# Door_Buttons.net
KiCad netlist of a schematic drawn in Altium Designer
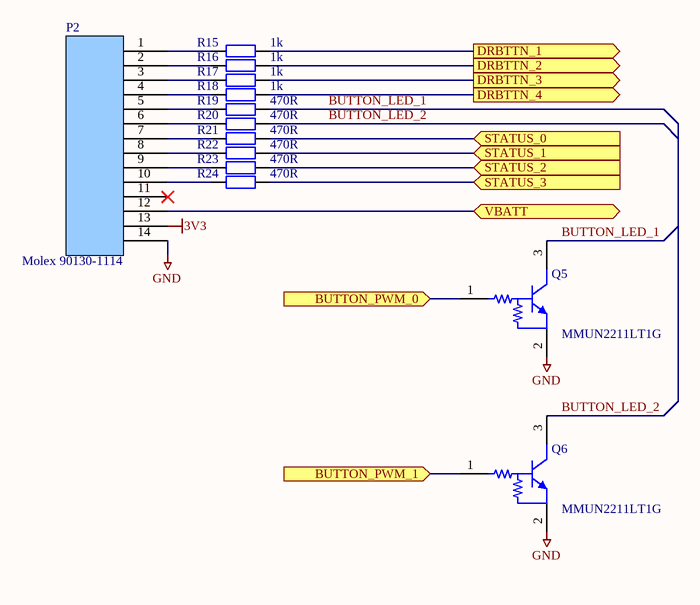
[diagram p0: Door Buttons.SchDoc]

(export (version "E")
  (design (tool "Eeschema 10.0.6"))
  (components
    (comp (ref "P2")
      (value "Molex 90130-1114")
      (footprint "PCB-642648-1")
      (description "Conn Shrouded Header HDR 14 POS 2.54mm Solder ST Thru-Hole C-Grid IIIáTray")
      (fields (field (name "MANUFACTURER PART NUMBER") "90130-1114"))
      (libsource (lib "FavoritesLibrary") (part "SYM-642648-1"))
    )
    (comp (ref "Q5")
      (value "MMUN2211LT1G")
      (footprint "ONSC-SOT-23-3-318-08_V")
      (libsource (lib "CommunityVault") (part "ONSC-BRT-NPN-B1E2C3-3"))
    )
    (comp (ref "Q6")
      (value "MMUN2211LT1G")
      (footprint "ONSC-SOT-23-3-318-08_V")
      (libsource (lib "CommunityVault") (part "ONSC-BRT-NPN-B1E2C3-3"))
    )
    (comp (ref "R15")
      (value "1k")
      (footprint "PCB-3652081-2")
      (description "GENERIC 0805 RESISTOR")
      (libsource (lib "FavoritesLibrary") (part "SYM-rprrpiwz7au7w5x5ojb2-1"))
    )
    (comp (ref "R16")
      (value "1k")
      (footprint "PCB-3652081-2")
      (description "GENERIC 0805 RESISTOR")
      (libsource (lib "FavoritesLibrary") (part "SYM-rprrpiwz7au7w5x5ojb2-1"))
    )
    (comp (ref "R17")
      (value "1k")
      (footprint "PCB-3652081-2")
      (description "GENERIC 0805 RESISTOR")
      (libsource (lib "FavoritesLibrary") (part "SYM-rprrpiwz7au7w5x5ojb2-1"))
    )
    (comp (ref "R18")
      (value "1k")
      (footprint "PCB-3652081-2")
      (description "GENERIC 0805 RESISTOR")
      (libsource (lib "FavoritesLibrary") (part "SYM-rprrpiwz7au7w5x5ojb2-1"))
    )
    (comp (ref "R19")
      (value "470R")
      (footprint "PCB-3652081-2")
      (description "GENERIC 0805 RESISTOR")
      (libsource (lib "FavoritesLibrary") (part "SYM-rprrpiwz7au7w5x5ojb2-1"))
    )
    (comp (ref "R20")
      (value "470R")
      (footprint "PCB-3652081-2")
      (description "GENERIC 0805 RESISTOR")
      (libsource (lib "FavoritesLibrary") (part "SYM-rprrpiwz7au7w5x5ojb2-1"))
    )
    (comp (ref "R21")
      (value "470R")
      (footprint "PCB-3652081-2")
      (description "GENERIC 0805 RESISTOR")
      (libsource (lib "FavoritesLibrary") (part "SYM-rprrpiwz7au7w5x5ojb2-1"))
    )
    (comp (ref "R22")
      (value "470R")
      (footprint "PCB-3652081-2")
      (description "GENERIC 0805 RESISTOR")
      (libsource (lib "FavoritesLibrary") (part "SYM-rprrpiwz7au7w5x5ojb2-1"))
    )
    (comp (ref "R23")
      (value "470R")
      (footprint "PCB-3652081-2")
      (description "GENERIC 0805 RESISTOR")
      (libsource (lib "FavoritesLibrary") (part "SYM-rprrpiwz7au7w5x5ojb2-1"))
    )
    (comp (ref "R24")
      (value "470R")
      (footprint "PCB-3652081-2")
      (description "GENERIC 0805 RESISTOR")
      (libsource (lib "FavoritesLibrary") (part "SYM-rprrpiwz7au7w5x5ojb2-1"))
    )
  )
  (nets
    (net (code "1") (name "/BUTTON_LED_1") (class "Default")
      (node (ref "Q5") (pin "3") (pinfunction "C_3") (pintype "passive"))
      (node (ref "R19") (pin "2") (pinfunction "2_2") (pintype "passive"))
    )
    (net (code "2") (name "/BUTTON_LED_2") (class "Default")
      (node (ref "Q6") (pin "3") (pinfunction "C_3") (pintype "passive"))
      (node (ref "R20") (pin "2") (pinfunction "2_2") (pintype "passive"))
    )
    (net (code "3") (name "/BUTTON_PWM_0") (class "Default")
      (node (ref "Q5") (pin "1") (pinfunction "B_1") (pintype "passive"))
    )
    (net (code "4") (name "/BUTTON_PWM_1") (class "Default")
      (node (ref "Q6") (pin "1") (pinfunction "B_1") (pintype "passive"))
    )
    (net (code "5") (name "/DRBTTN_1") (class "Default")
      (node (ref "R15") (pin "2") (pinfunction "2_2") (pintype "passive"))
    )
    (net (code "6") (name "/DRBTTN_2") (class "Default")
      (node (ref "R16") (pin "2") (pinfunction "2_2") (pintype "passive"))
    )
    (net (code "7") (name "/DRBTTN_3") (class "Default")
      (node (ref "R17") (pin "2") (pinfunction "2_2") (pintype "passive"))
    )
    (net (code "8") (name "/DRBTTN_4") (class "Default")
      (node (ref "R18") (pin "2") (pinfunction "2_2") (pintype "passive"))
    )
    (net (code "9") (name "/STATUS_0") (class "Default")
      (node (ref "R21") (pin "2") (pinfunction "2_2") (pintype "passive"))
    )
    (net (code "10") (name "/STATUS_1") (class "Default")
      (node (ref "R22") (pin "2") (pinfunction "2_2") (pintype "passive"))
    )
    (net (code "11") (name "/STATUS_2") (class "Default")
      (node (ref "R23") (pin "2") (pinfunction "2_2") (pintype "passive"))
    )
    (net (code "12") (name "/STATUS_3") (class "Default")
      (node (ref "R24") (pin "2") (pinfunction "2_2") (pintype "passive"))
    )
    (net (code "13") (name "/VBATT") (class "Default")
      (node (ref "P2") (pin "12") (pinfunction "12_12") (pintype "passive"))
    )
    (net (code "14") (name "3V3") (class "Default")
      (node (ref "P2") (pin "13") (pinfunction "13_13") (pintype "passive"))
    )
    (net (code "15") (name "GND") (class "Default")
      (node (ref "P2") (pin "14") (pinfunction "14_14") (pintype "passive"))
      (node (ref "Q5") (pin "2") (pinfunction "E_2") (pintype "passive"))
      (node (ref "Q6") (pin "2") (pinfunction "E_2") (pintype "passive"))
    )
    (net (code "16") (name "Net-(P2-Pad1)") (class "Default")
      (node (ref "P2") (pin "1") (pinfunction "1_1") (pintype "passive"))
      (node (ref "R15") (pin "1") (pinfunction "1_1") (pintype "passive"))
    )
    (net (code "17") (name "Net-(P2-Pad2)") (class "Default")
      (node (ref "P2") (pin "2") (pinfunction "2_2") (pintype "passive"))
      (node (ref "R16") (pin "1") (pinfunction "1_1") (pintype "passive"))
    )
    (net (code "18") (name "Net-(P2-Pad3)") (class "Default")
      (node (ref "P2") (pin "3") (pinfunction "3_3") (pintype "passive"))
      (node (ref "R17") (pin "1") (pinfunction "1_1") (pintype "passive"))
    )
    (net (code "19") (name "Net-(P2-Pad4)") (class "Default")
      (node (ref "P2") (pin "4") (pinfunction "4_4") (pintype "passive"))
      (node (ref "R18") (pin "1") (pinfunction "1_1") (pintype "passive"))
    )
    (net (code "20") (name "Net-(P2-Pad5)") (class "Default")
      (node (ref "P2") (pin "5") (pinfunction "5_5") (pintype "passive"))
      (node (ref "R19") (pin "1") (pinfunction "1_1") (pintype "passive"))
    )
    (net (code "21") (name "Net-(P2-Pad6)") (class "Default")
      (node (ref "P2") (pin "6") (pinfunction "6_6") (pintype "passive"))
      (node (ref "R20") (pin "1") (pinfunction "1_1") (pintype "passive"))
    )
    (net (code "22") (name "Net-(P2-Pad7)") (class "Default")
      (node (ref "P2") (pin "7") (pinfunction "7_7") (pintype "passive"))
      (node (ref "R21") (pin "1") (pinfunction "1_1") (pintype "passive"))
    )
    (net (code "23") (name "Net-(P2-Pad8)") (class "Default")
      (node (ref "P2") (pin "8") (pinfunction "8_8") (pintype "passive"))
      (node (ref "R22") (pin "1") (pinfunction "1_1") (pintype "passive"))
    )
    (net (code "24") (name "Net-(P2-Pad9)") (class "Default")
      (node (ref "P2") (pin "9") (pinfunction "9_9") (pintype "passive"))
      (node (ref "R23") (pin "1") (pinfunction "1_1") (pintype "passive"))
    )
    (net (code "25") (name "Net-(P2-Pad10)") (class "Default")
      (node (ref "P2") (pin "10") (pinfunction "10_10") (pintype "passive"))
      (node (ref "R24") (pin "1") (pinfunction "1_1") (pintype "passive"))
    )
    (net (code "26") (name "unconnected-(P2-Pad11)") (class "Default")
      (node (ref "P2") (pin "11") (pinfunction "11_11") (pintype "passive+no_connect"))
    )
  )
)
